# cSLIM-shield-LoRa.net
KiCad netlist of a schematic drawn in Altium Designer
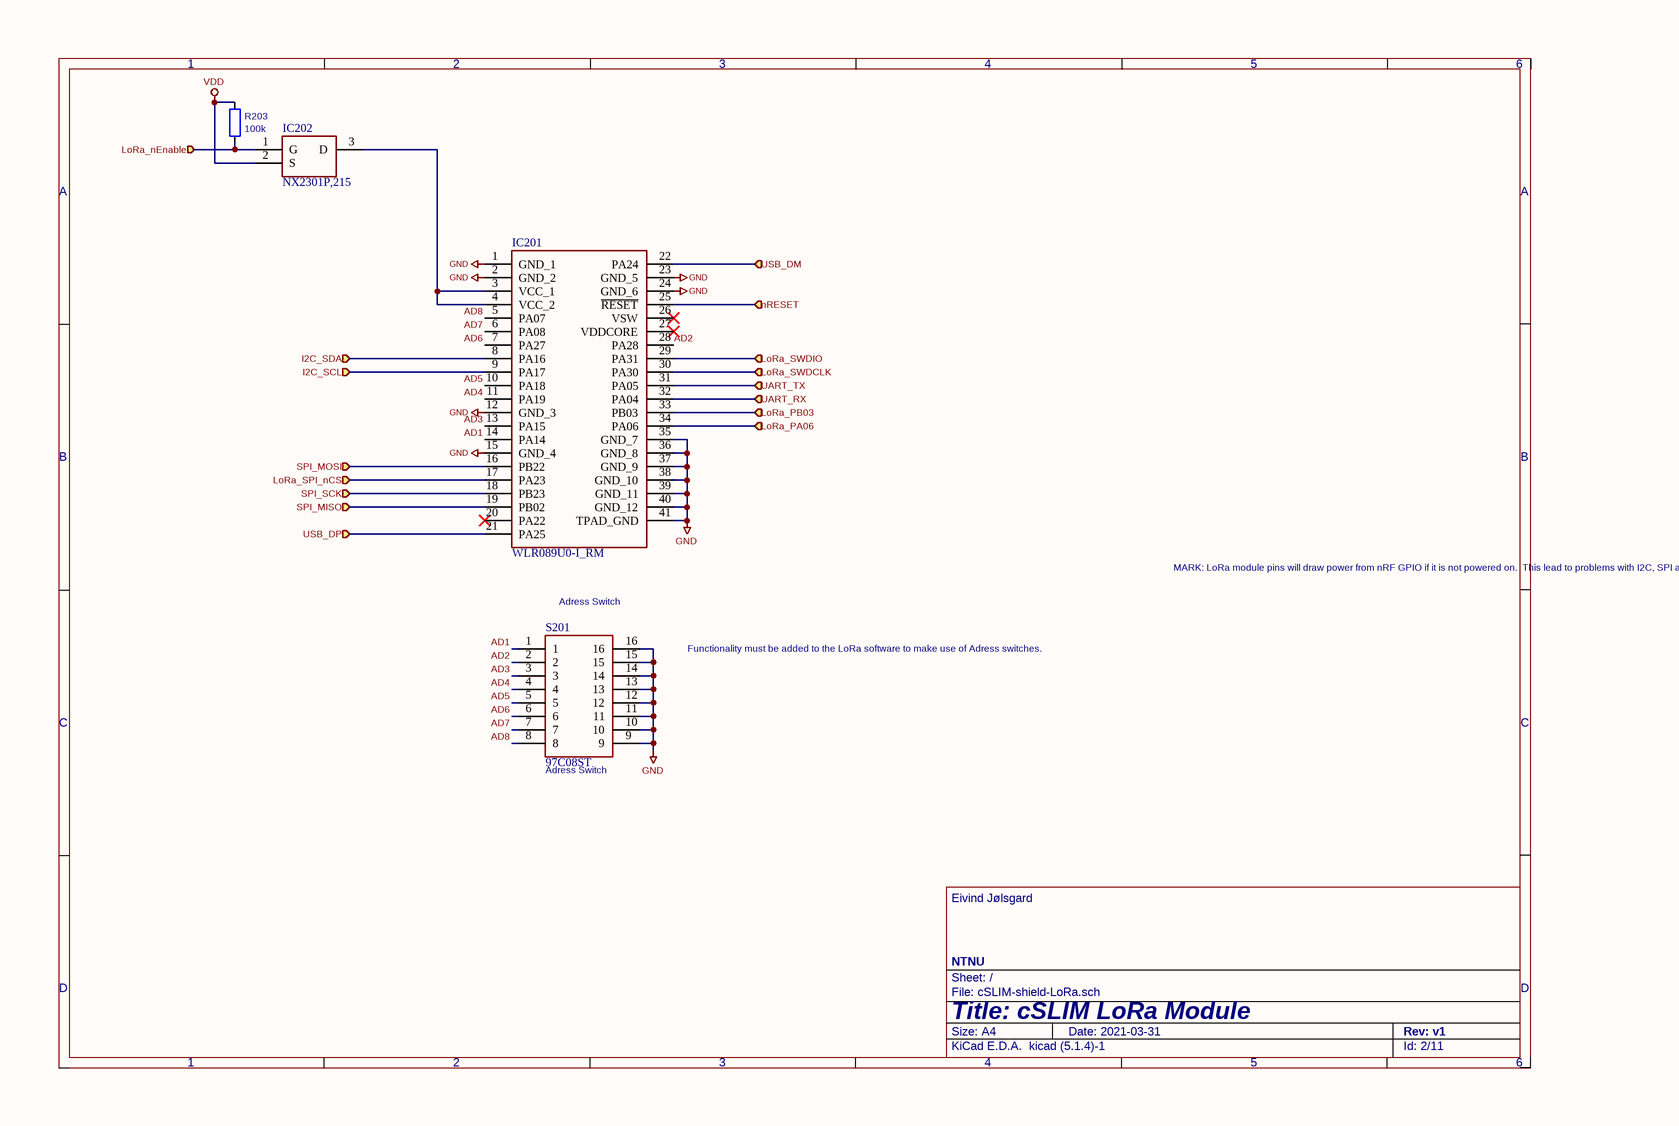
[diagram p0: cSLIM-shield-LoRa.SchDoc]

(export (version "E")
  (design (tool "Eeschema 10.0.6"))
  (components
    (comp (ref "IC201")
      (value "WLR089U0-I_RM")
      (footprint "cSLIM-SA:WLR089U0IRM")
      (description "Integrated Circuit")
      (fields
        (field (name "MANUFACTURER_PART_NUMBER") "WLR089U0-I/RM")
        (field (name "MOUSER PART NUMBER") "579-WLR089U0-I/RM")
      )
      (libsource (lib "cSLIM-SA") (part "WLR089U0-I_RM"))
    )
    (comp (ref "IC202")
      (value "NX2301P,215")
      (footprint "cSLIM-SA:SOT95P230X110-3N")
      (description "Integrated Circuit")
      (fields (field (name "MOUSER PART NUMBER") "771-NX2301P215"))
      (libsource (lib "cSLIM-SA") (part "NX2301P,215"))
    )
    (comp (ref "R203") (value "100k") (footprint "RESC1608X55N") (libsource (lib "cSLIM-SA") (part "R")))
    (comp (ref "S201")
      (value "97C08ST")
      (footprint "cSLIM-SA:SOIC127P671X170-16N")
      (description "Switch")
      (fields (field (name "MOUSER PART NUMBER") "706-97C08ST"))
      (libsource (lib "cSLIM-SA") (part "97C08ST"))
    )
  )
  (nets
    (net (code "1") (name "/AD1") (class "Default")
      (node (ref "IC201") (pin "14") (pinfunction "PA14_14") (pintype "passive"))
      (node (ref "S201") (pin "1") (pinfunction "1_1") (pintype "passive"))
    )
    (net (code "2") (name "/AD2") (class "Default")
      (node (ref "IC201") (pin "28") (pinfunction "PA28_28") (pintype "passive"))
      (node (ref "S201") (pin "2") (pinfunction "2_2") (pintype "passive"))
    )
    (net (code "3") (name "/AD3") (class "Default")
      (node (ref "IC201") (pin "13") (pinfunction "PA15_13") (pintype "passive"))
      (node (ref "S201") (pin "3") (pinfunction "3_3") (pintype "passive"))
    )
    (net (code "4") (name "/AD4") (class "Default")
      (node (ref "IC201") (pin "11") (pinfunction "PA19_11") (pintype "passive"))
      (node (ref "S201") (pin "4") (pinfunction "4_4") (pintype "passive"))
    )
    (net (code "5") (name "/AD5") (class "Default")
      (node (ref "IC201") (pin "10") (pinfunction "PA18_10") (pintype "passive"))
      (node (ref "S201") (pin "5") (pinfunction "5_5") (pintype "passive"))
    )
    (net (code "6") (name "/AD6") (class "Default")
      (node (ref "IC201") (pin "7") (pinfunction "PA27_7") (pintype "passive"))
      (node (ref "S201") (pin "6") (pinfunction "6_6") (pintype "passive"))
    )
    (net (code "7") (name "/AD7") (class "Default")
      (node (ref "IC201") (pin "6") (pinfunction "PA08_6") (pintype "passive"))
      (node (ref "S201") (pin "7") (pinfunction "7_7") (pintype "passive"))
    )
    (net (code "8") (name "/AD8") (class "Default")
      (node (ref "IC201") (pin "5") (pinfunction "PA07_5") (pintype "passive"))
      (node (ref "S201") (pin "8") (pinfunction "8_8") (pintype "passive"))
    )
    (net (code "9") (name "/I2C_SCL") (class "Default")
      (node (ref "IC201") (pin "9") (pinfunction "PA17_9") (pintype "passive"))
    )
    (net (code "10") (name "/I2C_SDA") (class "Default")
      (node (ref "IC201") (pin "8") (pinfunction "PA16_8") (pintype "passive"))
    )
    (net (code "11") (name "/LoRa_PA06") (class "Default")
      (node (ref "IC201") (pin "34") (pinfunction "PA06_34") (pintype "passive"))
    )
    (net (code "12") (name "/LoRa_PB03") (class "Default")
      (node (ref "IC201") (pin "33") (pinfunction "PB03_33") (pintype "passive"))
    )
    (net (code "13") (name "/LoRa_SPI_nCS") (class "Default")
      (node (ref "IC201") (pin "17") (pinfunction "PA23_17") (pintype "passive"))
    )
    (net (code "14") (name "/LoRa_SWDCLK") (class "Default")
      (node (ref "IC201") (pin "30") (pinfunction "PA30_30") (pintype "passive"))
    )
    (net (code "15") (name "/LoRa_SWDIO") (class "Default")
      (node (ref "IC201") (pin "29") (pinfunction "PA31_29") (pintype "passive"))
    )
    (net (code "16") (name "/LoRa_nEnable") (class "Default")
      (node (ref "IC202") (pin "1") (pinfunction "G_1") (pintype "passive"))
      (node (ref "R203") (pin "1") (pinfunction "1_1") (pintype "passive"))
    )
    (net (code "17") (name "/SPI_MISO") (class "Default")
      (node (ref "IC201") (pin "19") (pinfunction "PB02_19") (pintype "passive"))
    )
    (net (code "18") (name "/SPI_MOSI") (class "Default")
      (node (ref "IC201") (pin "16") (pinfunction "PB22_16") (pintype "passive"))
    )
    (net (code "19") (name "/SPI_SCK") (class "Default")
      (node (ref "IC201") (pin "18") (pinfunction "PB23_18") (pintype "passive"))
    )
    (net (code "20") (name "/UART_RX") (class "Default")
      (node (ref "IC201") (pin "32") (pinfunction "PA04_32") (pintype "passive"))
    )
    (net (code "21") (name "/UART_TX") (class "Default")
      (node (ref "IC201") (pin "31") (pinfunction "PA05_31") (pintype "passive"))
    )
    (net (code "22") (name "/USB_DM") (class "Default")
      (node (ref "IC201") (pin "22") (pinfunction "PA24_22") (pintype "passive"))
    )
    (net (code "23") (name "/USB_DP") (class "Default")
      (node (ref "IC201") (pin "21") (pinfunction "PA25_21") (pintype "passive"))
    )
    (net (code "24") (name "/nRESET") (class "Default")
      (node (ref "IC201") (pin "25") (pinfunction "~{RESET}_25") (pintype "passive"))
    )
    (net (code "25") (name "GND") (class "Default")
      (node (ref "IC201") (pin "1") (pinfunction "GND_1_1") (pintype "passive"))
      (node (ref "IC201") (pin "12") (pinfunction "GND_3_12") (pintype "passive"))
      (node (ref "IC201") (pin "15") (pinfunction "GND_4_15") (pintype "passive"))
      (node (ref "IC201") (pin "2") (pinfunction "GND_2_2") (pintype "passive"))
      (node (ref "IC201") (pin "23") (pinfunction "GND_5_23") (pintype "passive"))
      (node (ref "IC201") (pin "24") (pinfunction "GND_6_24") (pintype "passive"))
      (node (ref "IC201") (pin "35") (pinfunction "GND_7_35") (pintype "passive"))
      (node (ref "IC201") (pin "36") (pinfunction "GND_8_36") (pintype "passive"))
      (node (ref "IC201") (pin "37") (pinfunction "GND_9_37") (pintype "passive"))
      (node (ref "IC201") (pin "38") (pinfunction "GND_10_38") (pintype "passive"))
      (node (ref "IC201") (pin "39") (pinfunction "GND_11_39") (pintype "passive"))
      (node (ref "IC201") (pin "40") (pinfunction "GND_12_40") (pintype "passive"))
      (node (ref "IC201") (pin "41") (pinfunction "TPAD_GND_41") (pintype "passive"))
      (node (ref "S201") (pin "10") (pinfunction "10_10") (pintype "passive"))
      (node (ref "S201") (pin "11") (pinfunction "11_11") (pintype "passive"))
      (node (ref "S201") (pin "12") (pinfunction "12_12") (pintype "passive"))
      (node (ref "S201") (pin "13") (pinfunction "13_13") (pintype "passive"))
      (node (ref "S201") (pin "14") (pinfunction "14_14") (pintype "passive"))
      (node (ref "S201") (pin "15") (pinfunction "15_15") (pintype "passive"))
      (node (ref "S201") (pin "16") (pinfunction "16_16") (pintype "passive"))
      (node (ref "S201") (pin "9") (pinfunction "9_9") (pintype "passive"))
    )
    (net (code "26") (name "Net-(IC201-VCC_1)") (class "Default")
      (node (ref "IC201") (pin "3") (pinfunction "VCC_1_3") (pintype "passive"))
      (node (ref "IC201") (pin "4") (pinfunction "VCC_2_4") (pintype "passive"))
      (node (ref "IC202") (pin "3") (pinfunction "D_3") (pintype "passive"))
    )
    (net (code "27") (name "VDD") (class "Default")
      (node (ref "IC202") (pin "2") (pinfunction "S_2") (pintype "passive"))
      (node (ref "R203") (pin "2") (pinfunction "2_2") (pintype "passive"))
    )
    (net (code "28") (name "unconnected-(IC201-PA22-Pad20)") (class "Default")
      (node (ref "IC201") (pin "20") (pinfunction "PA22_20") (pintype "passive+no_connect"))
    )
    (net (code "29") (name "unconnected-(IC201-VDDCORE-Pad27)") (class "Default")
      (node (ref "IC201") (pin "27") (pinfunction "VDDCORE_27") (pintype "passive+no_connect"))
    )
    (net (code "30") (name "unconnected-(IC201-VSW-Pad26)") (class "Default")
      (node (ref "IC201") (pin "26") (pinfunction "VSW_26") (pintype "passive+no_connect"))
    )
  )
)
